# Noduino-iBaihe.net
KiCad netlist of a schematic drawn in EAGLE
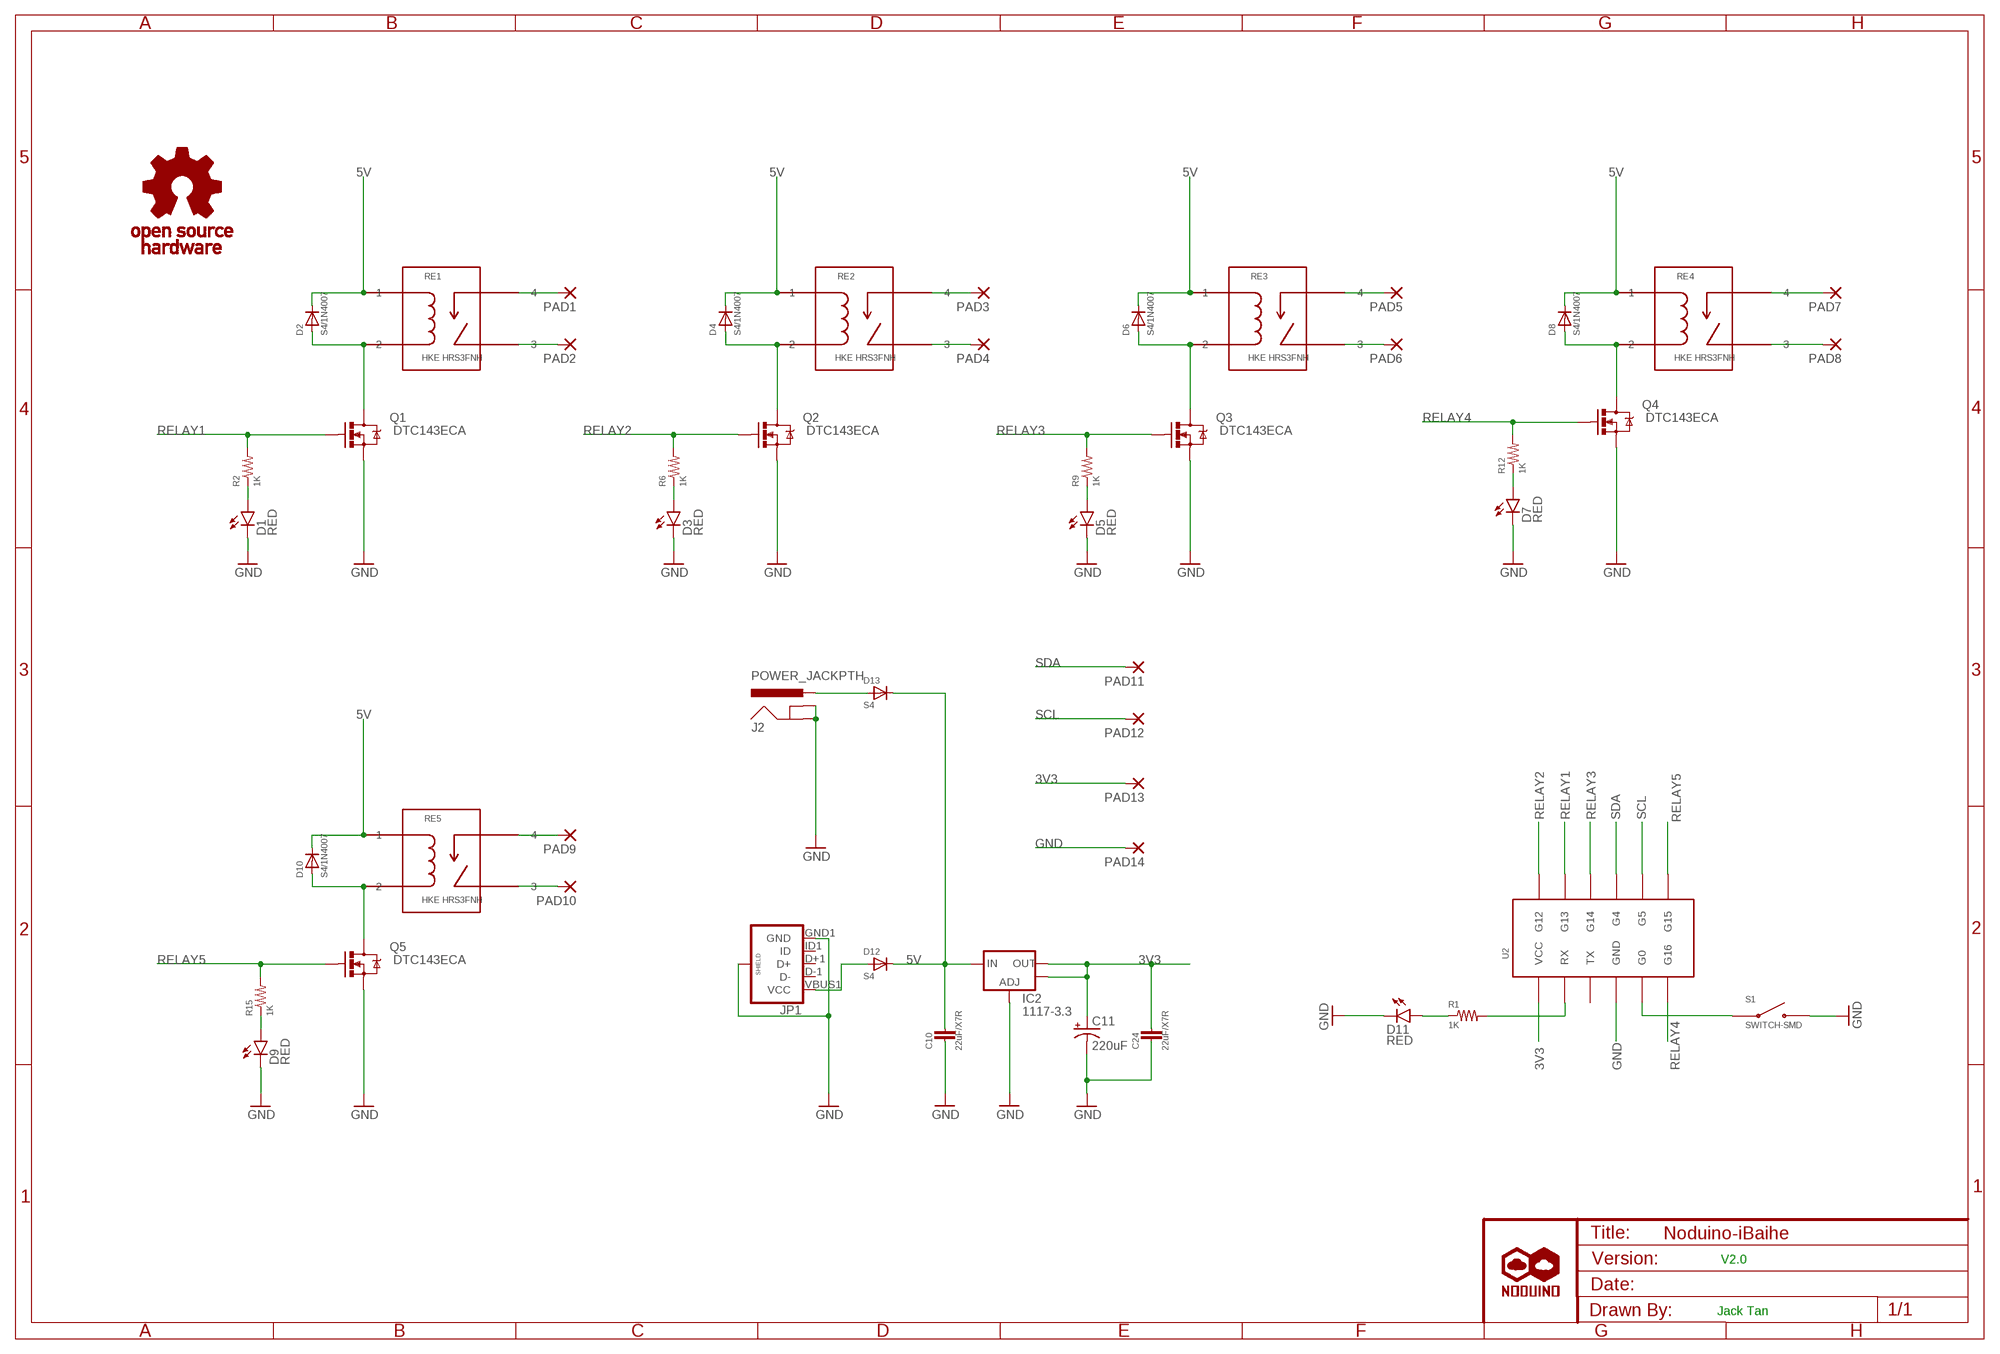
[diagram p0: schematic, sheet 1]

(export (version "E")
  (design (tool "Eeschema 10.0.6"))
  (components
    (comp (ref "C10")
      (value "22uF/X7R")
      (footprint "eagle-import:C1206")
      (libsource (lib "eagle-import") (part "CAP-C1206"))
    )
    (comp (ref "C11")
      (value "220uF")
      (footprint "eagle-import:EIA3528")
      (libsource (lib "eagle-import") (part "CAP_POL3528"))
    )
    (comp (ref "C24")
      (value "22uF/X7R")
      (footprint "eagle-import:C1206")
      (libsource (lib "eagle-import") (part "CAP-C1206"))
    )
    (comp (ref "D1")
      (value "RED")
      (footprint "eagle-import:LED-0603")
      (libsource (lib "eagle-import") (part "LED-RED0603"))
    )
    (comp (ref "D2")
      (value "S4/1N4007")
      (footprint "eagle-import:SOD-323")
      (libsource (lib "eagle-import") (part "DIODESOD"))
    )
    (comp (ref "D3")
      (value "RED")
      (footprint "eagle-import:LED-0603")
      (libsource (lib "eagle-import") (part "LED-RED0603"))
    )
    (comp (ref "D4")
      (value "S4/1N4007")
      (footprint "eagle-import:SOD-323")
      (libsource (lib "eagle-import") (part "DIODESOD"))
    )
    (comp (ref "D5")
      (value "RED")
      (footprint "eagle-import:LED-0603")
      (libsource (lib "eagle-import") (part "LED-RED0603"))
    )
    (comp (ref "D6")
      (value "S4/1N4007")
      (footprint "eagle-import:SOD-323")
      (libsource (lib "eagle-import") (part "DIODESOD"))
    )
    (comp (ref "D7")
      (value "RED")
      (footprint "eagle-import:LED-0603")
      (libsource (lib "eagle-import") (part "LED-RED0603"))
    )
    (comp (ref "D8")
      (value "S4/1N4007")
      (footprint "eagle-import:SOD-323")
      (libsource (lib "eagle-import") (part "DIODESOD"))
    )
    (comp (ref "D9")
      (value "RED")
      (footprint "eagle-import:LED-0603")
      (libsource (lib "eagle-import") (part "LED-RED0603"))
    )
    (comp (ref "D10")
      (value "S4/1N4007")
      (footprint "eagle-import:SOD-323")
      (libsource (lib "eagle-import") (part "DIODESOD"))
    )
    (comp (ref "D11")
      (value "RED")
      (footprint "eagle-import:LED-0603")
      (libsource (lib "eagle-import") (part "LED-RED0603"))
    )
    (comp (ref "D12")
      (value "S4")
      (footprint "eagle-import:SOD-323")
      (libsource (lib "eagle-import") (part "DIODESOD"))
    )
    (comp (ref "D13")
      (value "S4")
      (footprint "eagle-import:SOD-323")
      (libsource (lib "eagle-import") (part "DIODESOD"))
    )
    (comp (ref "IC2")
      (value "1117-3.3")
      (footprint "eagle-import:SOT223")
      (libsource (lib "eagle-import") (part "AMS1117SOT223"))
    )
    (comp (ref "J2")
      (value "POWER_JACKPTH")
      (footprint "eagle-import:POWER_JACK_PTH")
      (libsource (lib "eagle-import") (part "POWER_JACKPTH"))
    )
    (comp (ref "JP1")
      (value "USB_MICROB_PLUG")
      (footprint "eagle-import:MICROUSB-SMD-DIP")
      (libsource (lib "eagle-import") (part "USB_MICROB_PLUG"))
    )
    (comp (ref "PAD1")
      (value "2,15/1,0")
      (footprint "eagle-import:2,15_1,0")
      (libsource (lib "eagle-import") (part "2,15/1,0"))
    )
    (comp (ref "PAD2")
      (value "2,15/1,0")
      (footprint "eagle-import:2,15_1,0")
      (libsource (lib "eagle-import") (part "2,15/1,0"))
    )
    (comp (ref "PAD3")
      (value "2,15/1,0")
      (footprint "eagle-import:2,15_1,0")
      (libsource (lib "eagle-import") (part "2,15/1,0"))
    )
    (comp (ref "PAD4")
      (value "2,15/1,0")
      (footprint "eagle-import:2,15_1,0")
      (libsource (lib "eagle-import") (part "2,15/1,0"))
    )
    (comp (ref "PAD5")
      (value "2,15/1,0")
      (footprint "eagle-import:2,15_1,0")
      (libsource (lib "eagle-import") (part "2,15/1,0"))
    )
    (comp (ref "PAD6")
      (value "2,15/1,0")
      (footprint "eagle-import:2,15_1,0")
      (libsource (lib "eagle-import") (part "2,15/1,0"))
    )
    (comp (ref "PAD7")
      (value "2,15/1,0")
      (footprint "eagle-import:2,15_1,0")
      (libsource (lib "eagle-import") (part "2,15/1,0"))
    )
    (comp (ref "PAD8")
      (value "2,15/1,0")
      (footprint "eagle-import:2,15_1,0")
      (libsource (lib "eagle-import") (part "2,15/1,0"))
    )
    (comp (ref "PAD9")
      (value "2,15/1,0")
      (footprint "eagle-import:2,15_1,0")
      (libsource (lib "eagle-import") (part "2,15/1,0"))
    )
    (comp (ref "PAD10")
      (value "2,15/1,0")
      (footprint "eagle-import:2,15_1,0")
      (libsource (lib "eagle-import") (part "2,15/1,0"))
    )
    (comp (ref "PAD11")
      (value "1PIN0.8DRILL")
      (footprint "eagle-import:0.8_1.6")
      (libsource (lib "eagle-import") (part "1PIN0.8DRILL"))
    )
    (comp (ref "PAD12")
      (value "1PIN0.8DRILL")
      (footprint "eagle-import:0.8_1.6")
      (libsource (lib "eagle-import") (part "1PIN0.8DRILL"))
    )
    (comp (ref "PAD13")
      (value "1PIN0.8DRILL")
      (footprint "eagle-import:0.8_1.6")
      (libsource (lib "eagle-import") (part "1PIN0.8DRILL"))
    )
    (comp (ref "PAD14")
      (value "1PIN0.8DRILL")
      (footprint "eagle-import:0.8_1.6")
      (libsource (lib "eagle-import") (part "1PIN0.8DRILL"))
    )
    (comp (ref "Q1")
      (value "DTC143ECA")
      (footprint "eagle-import:SOT23-3")
      (libsource (lib "eagle-import") (part "MOSFET-N-SMD"))
    )
    (comp (ref "Q2")
      (value "DTC143ECA")
      (footprint "eagle-import:SOT23-3")
      (libsource (lib "eagle-import") (part "MOSFET-N-SMD"))
    )
    (comp (ref "Q3")
      (value "DTC143ECA")
      (footprint "eagle-import:SOT23-3")
      (libsource (lib "eagle-import") (part "MOSFET-N-SMD"))
    )
    (comp (ref "Q4")
      (value "DTC143ECA")
      (footprint "eagle-import:SOT23-3")
      (libsource (lib "eagle-import") (part "MOSFET-N-SMD"))
    )
    (comp (ref "Q5")
      (value "DTC143ECA")
      (footprint "eagle-import:SOT23-3")
      (libsource (lib "eagle-import") (part "MOSFET-N-SMD"))
    )
    (comp (ref "R1")
      (value "1K")
      (footprint "eagle-import:0603-RES")
      (libsource (lib "eagle-import") (part "0603-RESISTOR"))
    )
    (comp (ref "R2")
      (value "1K")
      (footprint "eagle-import:0603-RES")
      (libsource (lib "eagle-import") (part "0603-RESISTOR"))
    )
    (comp (ref "R6")
      (value "1K")
      (footprint "eagle-import:0603-RES")
      (libsource (lib "eagle-import") (part "0603-RESISTOR"))
    )
    (comp (ref "R9")
      (value "1K")
      (footprint "eagle-import:0603-RES")
      (libsource (lib "eagle-import") (part "0603-RESISTOR"))
    )
    (comp (ref "R12")
      (value "1K")
      (footprint "eagle-import:0603-RES")
      (libsource (lib "eagle-import") (part "0603-RESISTOR"))
    )
    (comp (ref "R15")
      (value "1K")
      (footprint "eagle-import:0603-RES")
      (libsource (lib "eagle-import") (part "0603-RESISTOR"))
    )
    (comp (ref "RE1")
      (value "HKE HRS3FNH")
      (footprint "eagle-import:HKE-HRS3FN")
      (libsource (lib "eagle-import") (part "HKE-HRS3FNH"))
    )
    (comp (ref "RE2")
      (value "HKE HRS3FNH")
      (footprint "eagle-import:HKE-HRS3FN")
      (libsource (lib "eagle-import") (part "HKE-HRS3FNH"))
    )
    (comp (ref "RE3")
      (value "HKE HRS3FNH")
      (footprint "eagle-import:HKE-HRS3FN")
      (libsource (lib "eagle-import") (part "HKE-HRS3FNH"))
    )
    (comp (ref "RE4")
      (value "HKE HRS3FNH")
      (footprint "eagle-import:HKE-HRS3FN")
      (libsource (lib "eagle-import") (part "HKE-HRS3FNH"))
    )
    (comp (ref "RE5")
      (value "HKE HRS3FNH")
      (footprint "eagle-import:HKE-HRS3FN")
      (libsource (lib "eagle-import") (part "HKE-HRS3FNH"))
    )
    (comp (ref "S1")
      (value "SWITCH-SMD")
      (footprint "eagle-import:TACTILE-SWITCH-1101NE")
      (libsource (lib "eagle-import") (part "SWITCH-SMD"))
    )
    (comp (ref "U$1")
      (value "NODUINO-LOGO-ALL")
      (footprint "eagle-import:NODUINO-ALL-1")
      (libsource (lib "eagle-import") (part "NODUINO-LOGO-ALL"))
    )
    (comp (ref "U$2")
      (value "OPEN_HARDWARE_LOGO")
      (footprint "eagle-import:OPEN_HARDWARE_LOGO")
      (libsource (lib "eagle-import") (part "OPEN_HARDWARE_LOGO"))
    )
    (comp (ref "U2")
      (value "MOD-SOCKET-V2.0")
      (footprint "eagle-import:MOD-PLUG-SOCKET-V2.0")
      (libsource (lib "eagle-import") (part "MOD-SOCKET-V2.0"))
    )
  )
  (nets
    (net (code "1") (name "/3V3") (class "Default")
      (node (ref "C11") (pin "A") (pinfunction "+_A") (pintype "passive"))
      (node (ref "C24") (pin "1") (pinfunction "1_1") (pintype "passive"))
      (node (ref "IC2") (pin "2") (pinfunction "OUT_2") (pintype "bidirectional"))
      (node (ref "IC2") (pin "4") (pinfunction "OUT_4") (pintype "bidirectional"))
      (node (ref "PAD13") (pin "1") (pinfunction "P_1") (pintype "passive"))
      (node (ref "U2") (pin "1") (pinfunction "VCC_1") (pintype "bidirectional"))
    )
    (net (code "2") (name "/5V") (class "Default")
      (node (ref "C10") (pin "1") (pinfunction "1_1") (pintype "passive"))
      (node (ref "D10") (pin "1") (pinfunction "C_1") (pintype "passive"))
      (node (ref "D12") (pin "1") (pinfunction "C_1") (pintype "passive"))
      (node (ref "D13") (pin "1") (pinfunction "C_1") (pintype "passive"))
      (node (ref "D2") (pin "1") (pinfunction "C_1") (pintype "passive"))
      (node (ref "D4") (pin "1") (pinfunction "C_1") (pintype "passive"))
      (node (ref "D6") (pin "1") (pinfunction "C_1") (pintype "passive"))
      (node (ref "D8") (pin "1") (pinfunction "C_1") (pintype "passive"))
      (node (ref "IC2") (pin "3") (pinfunction "IN_3") (pintype "input"))
      (node (ref "RE1") (pin "1") (pinfunction "1_1") (pintype "bidirectional"))
      (node (ref "RE2") (pin "1") (pinfunction "1_1") (pintype "bidirectional"))
      (node (ref "RE3") (pin "1") (pinfunction "1_1") (pintype "bidirectional"))
      (node (ref "RE4") (pin "1") (pinfunction "1_1") (pintype "bidirectional"))
      (node (ref "RE5") (pin "1") (pinfunction "1_1") (pintype "bidirectional"))
    )
    (net (code "3") (name "/RELAY1") (class "Default")
      (node (ref "Q1") (pin "1") (pinfunction "G_1") (pintype "passive"))
      (node (ref "R2") (pin "2") (pinfunction "2_2") (pintype "passive"))
      (node (ref "U2") (pin "11") (pinfunction "G13_11") (pintype "bidirectional"))
    )
    (net (code "4") (name "/RELAY2") (class "Default")
      (node (ref "Q2") (pin "1") (pinfunction "G_1") (pintype "passive"))
      (node (ref "R6") (pin "2") (pinfunction "2_2") (pintype "passive"))
      (node (ref "U2") (pin "12") (pinfunction "G12_12") (pintype "bidirectional"))
    )
    (net (code "5") (name "/RELAY3") (class "Default")
      (node (ref "Q3") (pin "1") (pinfunction "G_1") (pintype "passive"))
      (node (ref "R9") (pin "2") (pinfunction "2_2") (pintype "passive"))
      (node (ref "U2") (pin "10") (pinfunction "G14_10") (pintype "bidirectional"))
    )
    (net (code "6") (name "/RELAY4") (class "Default")
      (node (ref "Q4") (pin "1") (pinfunction "G_1") (pintype "passive"))
      (node (ref "R12") (pin "2") (pinfunction "2_2") (pintype "passive"))
      (node (ref "U2") (pin "6") (pinfunction "G16_6") (pintype "bidirectional"))
    )
    (net (code "7") (name "/RELAY5") (class "Default")
      (node (ref "Q5") (pin "1") (pinfunction "G_1") (pintype "passive"))
      (node (ref "R15") (pin "2") (pinfunction "2_2") (pintype "passive"))
      (node (ref "U2") (pin "7") (pinfunction "G15_7") (pintype "bidirectional"))
    )
    (net (code "8") (name "/SCL") (class "Default")
      (node (ref "PAD12") (pin "1") (pinfunction "P_1") (pintype "passive"))
      (node (ref "U2") (pin "8") (pinfunction "G5_8") (pintype "bidirectional"))
    )
    (net (code "9") (name "/SDA") (class "Default")
      (node (ref "PAD11") (pin "1") (pinfunction "P_1") (pintype "passive"))
      (node (ref "U2") (pin "9") (pinfunction "G4_9") (pintype "bidirectional"))
    )
    (net (code "10") (name "GND") (class "Default")
      (node (ref "C10") (pin "2") (pinfunction "2_2") (pintype "passive"))
      (node (ref "C11") (pin "C") (pinfunction "-_C") (pintype "passive"))
      (node (ref "C24") (pin "2") (pinfunction "2_2") (pintype "passive"))
      (node (ref "D1") (pin "C") (pinfunction "C_C") (pintype "passive"))
      (node (ref "D11") (pin "C") (pinfunction "C_C") (pintype "passive"))
      (node (ref "D3") (pin "C") (pinfunction "C_C") (pintype "passive"))
      (node (ref "D5") (pin "C") (pinfunction "C_C") (pintype "passive"))
      (node (ref "D7") (pin "C") (pinfunction "C_C") (pintype "passive"))
      (node (ref "D9") (pin "C") (pinfunction "C_C") (pintype "passive"))
      (node (ref "IC2") (pin "1") (pinfunction "ADJ_1") (pintype "input"))
      (node (ref "J2") (pin "GND") (pinfunction "GND_GND") (pintype "bidirectional"))
      (node (ref "J2") (pin "GNDBREAK") (pinfunction "GNDBREAK_GNDBREAK") (pintype "bidirectional"))
      (node (ref "JP1") (pin "GND1") (pinfunction "GND_GND1") (pintype "bidirectional"))
      (node (ref "JP1") (pin "P$1") (pinfunction "SHIELD_P$1") (pintype "bidirectional"))
      (node (ref "JP1") (pin "P$2") (pinfunction "SHIELD_P$2") (pintype "bidirectional"))
      (node (ref "JP1") (pin "P$3") (pinfunction "SHIELD_P$3") (pintype "bidirectional"))
      (node (ref "JP1") (pin "P$4") (pinfunction "SHIELD_P$4") (pintype "bidirectional"))
      (node (ref "PAD14") (pin "1") (pinfunction "P_1") (pintype "passive"))
      (node (ref "Q1") (pin "2") (pinfunction "S_2") (pintype "passive"))
      (node (ref "Q2") (pin "2") (pinfunction "S_2") (pintype "passive"))
      (node (ref "Q3") (pin "2") (pinfunction "S_2") (pintype "passive"))
      (node (ref "Q4") (pin "2") (pinfunction "S_2") (pintype "passive"))
      (node (ref "Q5") (pin "2") (pinfunction "S_2") (pintype "passive"))
      (node (ref "S1") (pin "P$1") (pinfunction "1_P$1") (pintype "bidirectional"))
      (node (ref "U2") (pin "4") (pinfunction "GND_4") (pintype "bidirectional"))
    )
    (net (code "11") (name "Net-(D1-PadA)") (class "Default")
      (node (ref "D1") (pin "A") (pinfunction "A_A") (pintype "passive"))
      (node (ref "R2") (pin "1") (pinfunction "1_1") (pintype "passive"))
    )
    (net (code "12") (name "Net-(D2-A)") (class "Default")
      (node (ref "D2") (pin "2") (pinfunction "A_2") (pintype "passive"))
      (node (ref "Q1") (pin "3") (pinfunction "D_3") (pintype "passive"))
      (node (ref "RE1") (pin "2") (pinfunction "2_2") (pintype "bidirectional"))
    )
    (net (code "13") (name "Net-(D3-PadA)") (class "Default")
      (node (ref "D3") (pin "A") (pinfunction "A_A") (pintype "passive"))
      (node (ref "R6") (pin "1") (pinfunction "1_1") (pintype "passive"))
    )
    (net (code "14") (name "Net-(D4-A)") (class "Default")
      (node (ref "D4") (pin "2") (pinfunction "A_2") (pintype "passive"))
      (node (ref "Q2") (pin "3") (pinfunction "D_3") (pintype "passive"))
      (node (ref "RE2") (pin "2") (pinfunction "2_2") (pintype "bidirectional"))
    )
    (net (code "15") (name "Net-(D5-PadA)") (class "Default")
      (node (ref "D5") (pin "A") (pinfunction "A_A") (pintype "passive"))
      (node (ref "R9") (pin "1") (pinfunction "1_1") (pintype "passive"))
    )
    (net (code "16") (name "Net-(D6-A)") (class "Default")
      (node (ref "D6") (pin "2") (pinfunction "A_2") (pintype "passive"))
      (node (ref "Q3") (pin "3") (pinfunction "D_3") (pintype "passive"))
      (node (ref "RE3") (pin "2") (pinfunction "2_2") (pintype "bidirectional"))
    )
    (net (code "17") (name "Net-(D7-PadA)") (class "Default")
      (node (ref "D7") (pin "A") (pinfunction "A_A") (pintype "passive"))
      (node (ref "R12") (pin "1") (pinfunction "1_1") (pintype "passive"))
    )
    (net (code "18") (name "Net-(D8-A)") (class "Default")
      (node (ref "D8") (pin "2") (pinfunction "A_2") (pintype "passive"))
      (node (ref "Q4") (pin "3") (pinfunction "D_3") (pintype "passive"))
      (node (ref "RE4") (pin "2") (pinfunction "2_2") (pintype "bidirectional"))
    )
    (net (code "19") (name "Net-(D9-PadA)") (class "Default")
      (node (ref "D9") (pin "A") (pinfunction "A_A") (pintype "passive"))
      (node (ref "R15") (pin "1") (pinfunction "1_1") (pintype "passive"))
    )
    (net (code "20") (name "Net-(D10-A)") (class "Default")
      (node (ref "D10") (pin "2") (pinfunction "A_2") (pintype "passive"))
      (node (ref "Q5") (pin "3") (pinfunction "D_3") (pintype "passive"))
      (node (ref "RE5") (pin "2") (pinfunction "2_2") (pintype "bidirectional"))
    )
    (net (code "21") (name "Net-(D11-PadA)") (class "Default")
      (node (ref "D11") (pin "A") (pinfunction "A_A") (pintype "passive"))
      (node (ref "R1") (pin "1") (pinfunction "1_1") (pintype "passive"))
    )
    (net (code "22") (name "Net-(D12-A)") (class "Default")
      (node (ref "D12") (pin "2") (pinfunction "A_2") (pintype "passive"))
      (node (ref "JP1") (pin "VBUS1") (pinfunction "VCC_VBUS1") (pintype "bidirectional"))
    )
    (net (code "23") (name "Net-(D13-A)") (class "Default")
      (node (ref "D13") (pin "2") (pinfunction "A_2") (pintype "passive"))
      (node (ref "J2") (pin "PWR") (pinfunction "PWR_PWR") (pintype "bidirectional"))
    )
    (net (code "24") (name "Net-(PAD1-P)") (class "Default")
      (node (ref "PAD1") (pin "1") (pinfunction "P_1") (pintype "passive"))
      (node (ref "RE1") (pin "4") (pinfunction "4_4") (pintype "bidirectional"))
    )
    (net (code "25") (name "Net-(PAD2-P)") (class "Default")
      (node (ref "PAD2") (pin "1") (pinfunction "P_1") (pintype "passive"))
      (node (ref "RE1") (pin "3") (pinfunction "3_3") (pintype "bidirectional"))
    )
    (net (code "26") (name "Net-(PAD3-P)") (class "Default")
      (node (ref "PAD3") (pin "1") (pinfunction "P_1") (pintype "passive"))
      (node (ref "RE2") (pin "4") (pinfunction "4_4") (pintype "bidirectional"))
    )
    (net (code "27") (name "Net-(PAD4-P)") (class "Default")
      (node (ref "PAD4") (pin "1") (pinfunction "P_1") (pintype "passive"))
      (node (ref "RE2") (pin "3") (pinfunction "3_3") (pintype "bidirectional"))
    )
    (net (code "28") (name "Net-(PAD5-P)") (class "Default")
      (node (ref "PAD5") (pin "1") (pinfunction "P_1") (pintype "passive"))
      (node (ref "RE3") (pin "4") (pinfunction "4_4") (pintype "bidirectional"))
    )
    (net (code "29") (name "Net-(PAD6-P)") (class "Default")
      (node (ref "PAD6") (pin "1") (pinfunction "P_1") (pintype "passive"))
      (node (ref "RE3") (pin "3") (pinfunction "3_3") (pintype "bidirectional"))
    )
    (net (code "30") (name "Net-(PAD7-P)") (class "Default")
      (node (ref "PAD7") (pin "1") (pinfunction "P_1") (pintype "passive"))
      (node (ref "RE4") (pin "4") (pinfunction "4_4") (pintype "bidirectional"))
    )
    (net (code "31") (name "Net-(PAD8-P)") (class "Default")
      (node (ref "PAD8") (pin "1") (pinfunction "P_1") (pintype "passive"))
      (node (ref "RE4") (pin "3") (pinfunction "3_3") (pintype "bidirectional"))
    )
    (net (code "32") (name "Net-(PAD9-P)") (class "Default")
      (node (ref "PAD9") (pin "1") (pinfunction "P_1") (pintype "passive"))
      (node (ref "RE5") (pin "4") (pinfunction "4_4") (pintype "bidirectional"))
    )
    (net (code "33") (name "Net-(PAD10-P)") (class "Default")
      (node (ref "PAD10") (pin "1") (pinfunction "P_1") (pintype "passive"))
      (node (ref "RE5") (pin "3") (pinfunction "3_3") (pintype "bidirectional"))
    )
    (net (code "34") (name "Net-(S1-2)") (class "Default")
      (node (ref "S1") (pin "P$2") (pinfunction "2_P$2") (pintype "bidirectional"))
      (node (ref "U2") (pin "5") (pinfunction "G0_5") (pintype "bidirectional"))
    )
    (net (code "35") (name "Net-(U2-RX)") (class "Default")
      (node (ref "R1") (pin "2") (pinfunction "2_2") (pintype "passive"))
      (node (ref "U2") (pin "2") (pinfunction "RX_2") (pintype "bidirectional"))
    )
    (net (code "36") (name "unconnected-(JP1-D+-PadD+1)") (class "Default")
      (node (ref "JP1") (pin "D+1") (pinfunction "D+_D+1") (pintype "bidirectional"))
    )
    (net (code "37") (name "unconnected-(JP1-D--PadD-1)") (class "Default")
      (node (ref "JP1") (pin "D-1") (pinfunction "D-_D-1") (pintype "bidirectional"))
    )
    (net (code "38") (name "unconnected-(JP1-ID-PadID1)") (class "Default")
      (node (ref "JP1") (pin "ID1") (pinfunction "ID_ID1") (pintype "bidirectional"))
    )
    (net (code "39") (name "unconnected-(U2-TX-Pad3)") (class "Default")
      (node (ref "U2") (pin "3") (pinfunction "TX_3") (pintype "bidirectional"))
    )
  )
)
